# ATMEGA16v4.net
KiCad netlist of a schematic drawn in EAGLE
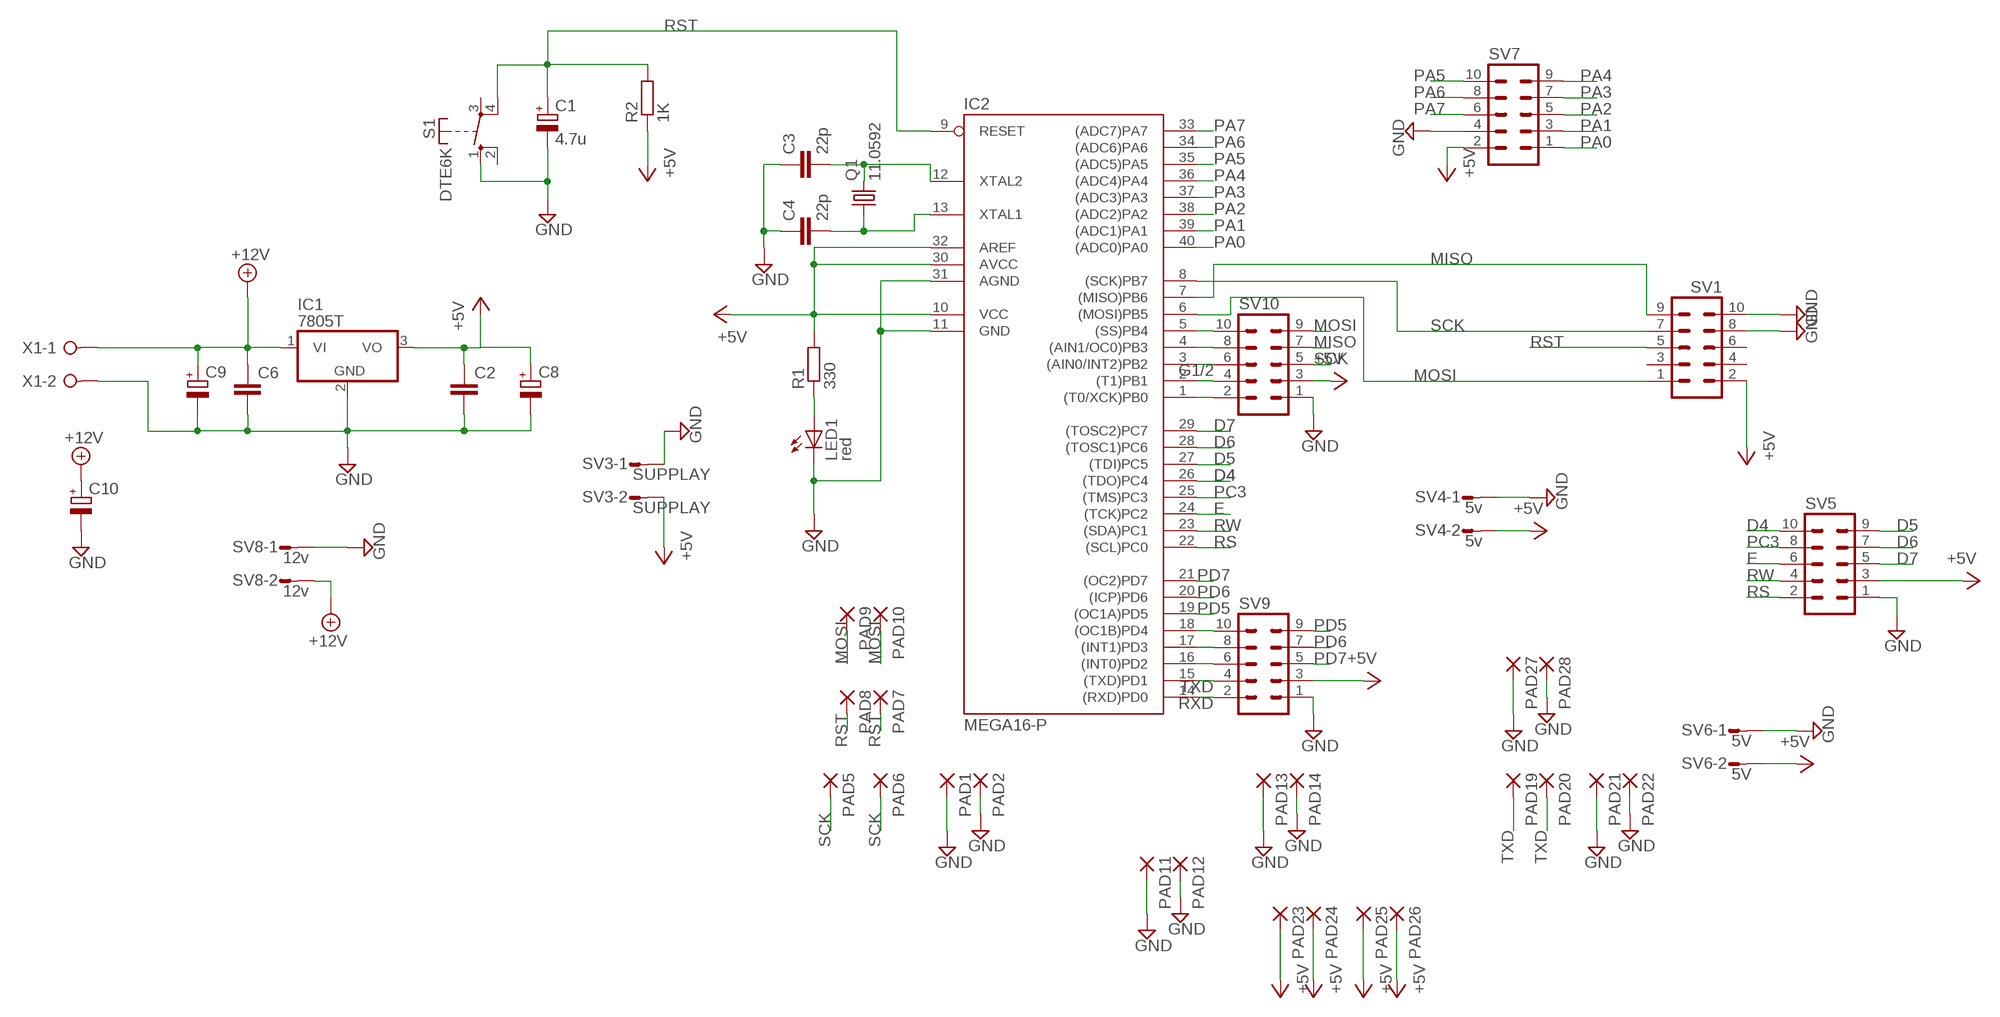
[diagram p0: schematic, sheet 1]
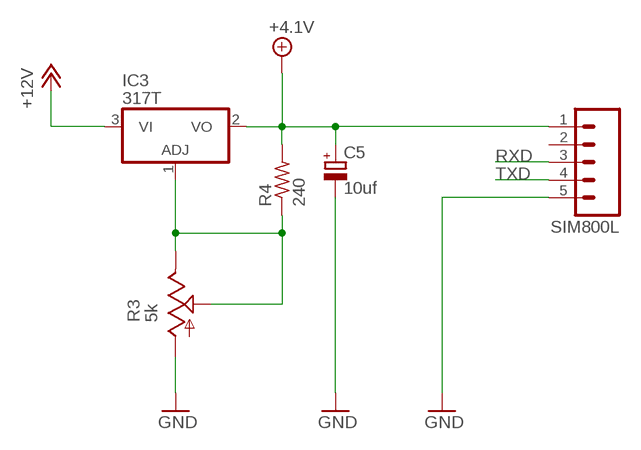
[diagram p1: schematic, sheet 2]

(export (version "E")
  (design (tool "Eeschema 10.0.6"))
  (components
    (comp (ref "C1")
      (value "4.7u")
      (footprint "eagle-import:E2-5")
      (libsource (lib "eagle-import") (part "CPOL-EUE2-5"))
    )
    (comp (ref "C2")
      (value "C-EU050-050X075")
      (footprint "eagle-import:C050-050X075")
      (libsource (lib "eagle-import") (part "C-EU050-050X075"))
    )
    (comp (ref "C3")
      (value "22p")
      (footprint "eagle-import:C025-040X050")
      (libsource (lib "eagle-import") (part "resistor_C-EU025-040X050"))
    )
    (comp (ref "C4")
      (value "22p")
      (footprint "eagle-import:C025-040X050")
      (libsource (lib "eagle-import") (part "resistor_C-EU025-040X050"))
    )
    (comp (ref "C6")
      (value "C-EU050-050X075")
      (footprint "eagle-import:C050-050X075")
      (libsource (lib "eagle-import") (part "C-EU050-050X075"))
    )
    (comp (ref "C8")
      (value "CPOL-EUE2.5-7")
      (footprint "eagle-import:E2,5-7")
      (libsource (lib "eagle-import") (part "CPOL-EUE2.5-7"))
    )
    (comp (ref "C9")
      (value "CPOL-EUE2.5-7")
      (footprint "eagle-import:E2,5-7")
      (libsource (lib "eagle-import") (part "CPOL-EUE2.5-7"))
    )
    (comp (ref "C10")
      (value "CPOL-EUE5-13")
      (footprint "eagle-import:E5-13")
      (libsource (lib "eagle-import") (part "CPOL-EUE5-13"))
    )
    (comp (ref "IC1")
      (value "7805T")
      (footprint "eagle-import:TO220H")
      (libsource (lib "eagle-import") (part "78T05"))
    )
    (comp (ref "IC2")
      (value "MEGA16-P")
      (footprint "eagle-import:DIL40")
      (libsource (lib "eagle-import") (part "MEGA16-P"))
    )
    (comp (ref "LED1")
      (value "red")
      (footprint "eagle-import:LED3MM")
      (libsource (lib "eagle-import") (part "LED3MM"))
    )
    (comp (ref "PAD1")
      (value "1,6/0,9")
      (footprint "eagle-import:1,6_0,9")
      (libsource (lib "eagle-import") (part "1,6/0,9"))
    )
    (comp (ref "PAD2")
      (value "1,6/0,9")
      (footprint "eagle-import:1,6_0,9")
      (libsource (lib "eagle-import") (part "1,6/0,9"))
    )
    (comp (ref "PAD5")
      (value "1,6/0,9")
      (footprint "eagle-import:1,6_0,9")
      (libsource (lib "eagle-import") (part "1,6/0,9"))
    )
    (comp (ref "PAD6")
      (value "1,6/0,9")
      (footprint "eagle-import:1,6_0,9")
      (libsource (lib "eagle-import") (part "1,6/0,9"))
    )
    (comp (ref "PAD7")
      (value "1,6/0,9")
      (footprint "eagle-import:1,6_0,9")
      (libsource (lib "eagle-import") (part "1,6/0,9"))
    )
    (comp (ref "PAD8")
      (value "1,6/0,9")
      (footprint "eagle-import:1,6_0,9")
      (libsource (lib "eagle-import") (part "1,6/0,9"))
    )
    (comp (ref "PAD9")
      (value "1,6/0,9")
      (footprint "eagle-import:1,6_0,9")
      (libsource (lib "eagle-import") (part "1,6/0,9"))
    )
    (comp (ref "PAD10")
      (value "1,6/0,9")
      (footprint "eagle-import:1,6_0,9")
      (libsource (lib "eagle-import") (part "1,6/0,9"))
    )
    (comp (ref "PAD11")
      (value "1,6/0,9")
      (footprint "eagle-import:1,6_0,9")
      (libsource (lib "eagle-import") (part "1,6/0,9"))
    )
    (comp (ref "PAD12")
      (value "1,6/0,9")
      (footprint "eagle-import:1,6_0,9")
      (libsource (lib "eagle-import") (part "1,6/0,9"))
    )
    (comp (ref "PAD13")
      (value "1,6/0,9")
      (footprint "eagle-import:1,6_0,9")
      (libsource (lib "eagle-import") (part "1,6/0,9"))
    )
    (comp (ref "PAD14")
      (value "1,6/0,9")
      (footprint "eagle-import:1,6_0,9")
      (libsource (lib "eagle-import") (part "1,6/0,9"))
    )
    (comp (ref "PAD19")
      (value "1,6/0,9")
      (footprint "eagle-import:1,6_0,9")
      (libsource (lib "eagle-import") (part "1,6/0,9"))
    )
    (comp (ref "PAD20")
      (value "1,6/0,9")
      (footprint "eagle-import:1,6_0,9")
      (libsource (lib "eagle-import") (part "1,6/0,9"))
    )
    (comp (ref "PAD21")
      (value "1,6/0,9")
      (footprint "eagle-import:1,6_0,9")
      (libsource (lib "eagle-import") (part "1,6/0,9"))
    )
    (comp (ref "PAD22")
      (value "1,6/0,9")
      (footprint "eagle-import:1,6_0,9")
      (libsource (lib "eagle-import") (part "1,6/0,9"))
    )
    (comp (ref "PAD23")
      (value "1,6/0,9")
      (footprint "eagle-import:1,6_0,9")
      (libsource (lib "eagle-import") (part "1,6/0,9"))
    )
    (comp (ref "PAD24")
      (value "1,6/0,9")
      (footprint "eagle-import:1,6_0,9")
      (libsource (lib "eagle-import") (part "1,6/0,9"))
    )
    (comp (ref "PAD25")
      (value "1,6/0,9")
      (footprint "eagle-import:1,6_0,9")
      (libsource (lib "eagle-import") (part "1,6/0,9"))
    )
    (comp (ref "PAD26")
      (value "1,6/0,9")
      (footprint "eagle-import:1,6_0,9")
      (libsource (lib "eagle-import") (part "1,6/0,9"))
    )
    (comp (ref "PAD27")
      (value "1,6/0,9")
      (footprint "eagle-import:1,6_0,9")
      (libsource (lib "eagle-import") (part "1,6/0,9"))
    )
    (comp (ref "PAD28")
      (value "1,6/0,9")
      (footprint "eagle-import:1,6_0,9")
      (libsource (lib "eagle-import") (part "1,6/0,9"))
    )
    (comp (ref "Q1")
      (value "11.0592")
      (footprint "eagle-import:HC49U-V")
      (libsource (lib "eagle-import") (part "CRYSTALHC49U-V"))
    )
    (comp (ref "R1")
      (value "330")
      (footprint "eagle-import:0309_12")
      (libsource (lib "eagle-import") (part "R-EU_0309/12"))
    )
    (comp (ref "R2")
      (value "1K")
      (footprint "eagle-import:0309_12")
      (libsource (lib "eagle-import") (part "R-EU_0309/12"))
    )
    (comp (ref "S1")
      (value "DTE6K")
      (footprint "eagle-import:DTE6K")
      (libsource (lib "eagle-import") (part "DTE6K"))
    )
    (comp (ref "SV1")
      (value "ML10")
      (footprint "eagle-import:ML10")
      (libsource (lib "eagle-import") (part "ML10"))
    )
    (comp (ref "SV3")
      (value "SUPPLAY")
      (footprint "eagle-import:L02P")
      (libsource (lib "eagle-import") (part "L02P"))
    )
    (comp (ref "SV4")
      (value "5v")
      (footprint "eagle-import:L02P")
      (libsource (lib "eagle-import") (part "L02P"))
    )
    (comp (ref "SV5")
      (value "ML10")
      (footprint "eagle-import:ML10")
      (libsource (lib "eagle-import") (part "ML10"))
    )
    (comp (ref "SV6")
      (value "5V")
      (footprint "eagle-import:L02P")
      (libsource (lib "eagle-import") (part "L02P"))
    )
    (comp (ref "SV7")
      (value "ML10")
      (footprint "eagle-import:ML10")
      (libsource (lib "eagle-import") (part "ML10"))
    )
    (comp (ref "SV8")
      (value "12v")
      (footprint "eagle-import:L02P")
      (libsource (lib "eagle-import") (part "L02P"))
    )
    (comp (ref "SV9")
      (value "ML10")
      (footprint "eagle-import:ML10")
      (libsource (lib "eagle-import") (part "ML10"))
    )
    (comp (ref "SV10")
      (value "ML10")
      (footprint "eagle-import:ML10")
      (libsource (lib "eagle-import") (part "ML10"))
    )
    (comp (ref "X1")
      (value "W237-02P")
      (footprint "eagle-import:W237-132")
      (libsource (lib "eagle-import") (part "W237-02P"))
    )
    (comp (ref "C5")
      (value "10uf")
      (footprint "eagle-import:E2,5-5")
      (libsource (lib "eagle-import") (part "CPOL-EUE2.5-5"))
    )
    (comp (ref "IC3")
      (value "317T")
      (footprint "eagle-import:TO220H")
      (libsource (lib "eagle-import") (part "317T"))
    )
    (comp (ref "R3")
      (value "5k")
      (footprint "eagle-import:CA6V")
      (libsource (lib "eagle-import") (part "TRIM_US-CA6V"))
    )
    (comp (ref "R4")
      (value "240")
      (footprint "eagle-import:0207_12")
      (libsource (lib "eagle-import") (part "R-US_0207/12"))
    )
    (comp (ref "SIM800L")
      (value "M05")
      (footprint "eagle-import:05P")
      (libsource (lib "eagle-import") (part "M05"))
    )
  )
  (nets
    (net (code "1") (name "+4.1V") (class "Default")
      (node (ref "C5") (pin "+") (pinfunction "+_+") (pintype "passive"))
      (node (ref "IC3") (pin "2") (pinfunction "VO_2") (pintype "passive"))
      (node (ref "R4") (pin "2") (pinfunction "2_2") (pintype "passive"))
      (node (ref "SIM800L") (pin "1") (pinfunction "1_1") (pintype "passive"))
    )
    (net (code "2") (name "+5V") (class "Default")
      (node (ref "C2") (pin "1") (pinfunction "1_1") (pintype "passive"))
      (node (ref "C8") (pin "+") (pinfunction "+_+") (pintype "passive"))
      (node (ref "IC1") (pin "3") (pinfunction "VO_3") (pintype "passive"))
      (node (ref "IC2") (pin "10") (pinfunction "VCC_10") (pintype "power_in"))
      (node (ref "IC2") (pin "30") (pinfunction "AVCC_30") (pintype "power_in"))
      (node (ref "IC2") (pin "32") (pinfunction "AREF_32") (pintype "passive"))
      (node (ref "PAD23") (pin "1") (pinfunction "P_1") (pintype "passive"))
      (node (ref "PAD24") (pin "1") (pinfunction "P_1") (pintype "passive"))
      (node (ref "PAD25") (pin "1") (pinfunction "P_1") (pintype "passive"))
      (node (ref "PAD26") (pin "1") (pinfunction "P_1") (pintype "passive"))
      (node (ref "R1") (pin "2") (pinfunction "2_2") (pintype "passive"))
      (node (ref "R2") (pin "1") (pinfunction "1_1") (pintype "passive"))
      (node (ref "SV1") (pin "2") (pinfunction "2_2") (pintype "passive"))
      (node (ref "SV10") (pin "3") (pinfunction "3_3") (pintype "passive"))
      (node (ref "SV3") (pin "2") (pinfunction "S_2") (pintype "passive"))
      (node (ref "SV4") (pin "2") (pinfunction "S_2") (pintype "passive"))
      (node (ref "SV5") (pin "3") (pinfunction "3_3") (pintype "passive"))
      (node (ref "SV6") (pin "2") (pinfunction "S_2") (pintype "passive"))
      (node (ref "SV7") (pin "2") (pinfunction "2_2") (pintype "passive"))
      (node (ref "SV9") (pin "3") (pinfunction "3_3") (pintype "passive"))
    )
    (net (code "3") (name "+12V") (class "Default")
      (node (ref "C10") (pin "+") (pinfunction "+_+") (pintype "passive"))
      (node (ref "C6") (pin "1") (pinfunction "1_1") (pintype "passive"))
      (node (ref "C9") (pin "+") (pinfunction "+_+") (pintype "passive"))
      (node (ref "IC1") (pin "1") (pinfunction "VI_1") (pintype "input"))
      (node (ref "IC3") (pin "3") (pinfunction "VI_3") (pintype "input"))
      (node (ref "SV8") (pin "2") (pinfunction "S_2") (pintype "passive"))
      (node (ref "X1") (pin "1") (pinfunction "KL_1") (pintype "passive"))
    )
    (net (code "4") (name "D4") (class "Default")
      (node (ref "IC2") (pin "26") (pinfunction "(TDO)PC4_26") (pintype "bidirectional"))
      (node (ref "SV5") (pin "10") (pinfunction "10_10") (pintype "passive"))
    )
    (net (code "5") (name "D5") (class "Default")
      (node (ref "IC2") (pin "27") (pinfunction "(TDI)PC5_27") (pintype "bidirectional"))
      (node (ref "SV5") (pin "9") (pinfunction "9_9") (pintype "passive"))
    )
    (net (code "6") (name "D6") (class "Default")
      (node (ref "IC2") (pin "28") (pinfunction "(TOSC1)PC6_28") (pintype "bidirectional"))
      (node (ref "SV5") (pin "7") (pinfunction "7_7") (pintype "passive"))
    )
    (net (code "7") (name "D7") (class "Default")
      (node (ref "IC2") (pin "29") (pinfunction "(TOSC2)PC7_29") (pintype "bidirectional"))
      (node (ref "SV5") (pin "5") (pinfunction "5_5") (pintype "passive"))
    )
    (net (code "8") (name "E") (class "Default")
      (node (ref "IC2") (pin "24") (pinfunction "(TCK)PC2_24") (pintype "bidirectional"))
      (node (ref "SV5") (pin "6") (pinfunction "6_6") (pintype "passive"))
    )
    (net (code "9") (name "G1{slash}2") (class "Default")
      (node (ref "IC2") (pin "2") (pinfunction "(T1)PB1_2") (pintype "bidirectional"))
      (node (ref "SV10") (pin "4") (pinfunction "4_4") (pintype "passive"))
    )
    (net (code "10") (name "GND") (class "Default")
      (node (ref "C1") (pin "-") (pinfunction "-_-") (pintype "passive"))
      (node (ref "C10") (pin "-") (pinfunction "-_-") (pintype "passive"))
      (node (ref "C2") (pin "2") (pinfunction "2_2") (pintype "passive"))
      (node (ref "C3") (pin "1") (pinfunction "1_1") (pintype "passive"))
      (node (ref "C4") (pin "1") (pinfunction "1_1") (pintype "passive"))
      (node (ref "C5") (pin "-") (pinfunction "-_-") (pintype "passive"))
      (node (ref "C6") (pin "2") (pinfunction "2_2") (pintype "passive"))
      (node (ref "C8") (pin "-") (pinfunction "-_-") (pintype "passive"))
      (node (ref "C9") (pin "-") (pinfunction "-_-") (pintype "passive"))
      (node (ref "IC1") (pin "2") (pinfunction "GND_2") (pintype "passive"))
      (node (ref "IC2") (pin "11") (pinfunction "GND_11") (pintype "power_in"))
      (node (ref "IC2") (pin "31") (pinfunction "AGND_31") (pintype "power_in"))
      (node (ref "LED1") (pin "K") (pinfunction "C_K") (pintype "passive"))
      (node (ref "PAD1") (pin "1") (pinfunction "P_1") (pintype "passive"))
      (node (ref "PAD11") (pin "1") (pinfunction "P_1") (pintype "passive"))
      (node (ref "PAD12") (pin "1") (pinfunction "P_1") (pintype "passive"))
      (node (ref "PAD13") (pin "1") (pinfunction "P_1") (pintype "passive"))
      (node (ref "PAD14") (pin "1") (pinfunction "P_1") (pintype "passive"))
      (node (ref "PAD2") (pin "1") (pinfunction "P_1") (pintype "passive"))
      (node (ref "PAD21") (pin "1") (pinfunction "P_1") (pintype "passive"))
      (node (ref "PAD22") (pin "1") (pinfunction "P_1") (pintype "passive"))
      (node (ref "PAD27") (pin "1") (pinfunction "P_1") (pintype "passive"))
      (node (ref "PAD28") (pin "1") (pinfunction "P_1") (pintype "passive"))
      (node (ref "R3") (pin "A") (pinfunction "A_A") (pintype "passive"))
      (node (ref "S1") (pin "1") (pinfunction "S_1") (pintype "passive"))
      (node (ref "SIM800L") (pin "5") (pinfunction "5_5") (pintype "passive"))
      (node (ref "SV1") (pin "10") (pinfunction "10_10") (pintype "passive"))
      (node (ref "SV1") (pin "8") (pinfunction "8_8") (pintype "passive"))
      (node (ref "SV10") (pin "1") (pinfunction "1_1") (pintype "passive"))
      (node (ref "SV3") (pin "1") (pinfunction "S_1") (pintype "passive"))
      (node (ref "SV4") (pin "1") (pinfunction "S_1") (pintype "passive"))
      (node (ref "SV5") (pin "1") (pinfunction "1_1") (pintype "passive"))
      (node (ref "SV6") (pin "1") (pinfunction "S_1") (pintype "passive"))
      (node (ref "SV7") (pin "4") (pinfunction "4_4") (pintype "passive"))
      (node (ref "SV8") (pin "1") (pinfunction "S_1") (pintype "passive"))
      (node (ref "SV9") (pin "1") (pinfunction "1_1") (pintype "passive"))
      (node (ref "X1") (pin "2") (pinfunction "KL_2") (pintype "passive"))
    )
    (net (code "11") (name "MISO") (class "Default")
      (node (ref "IC2") (pin "7") (pinfunction "(MISO)PB6_7") (pintype "bidirectional"))
      (node (ref "SV1") (pin "9") (pinfunction "9_9") (pintype "passive"))
      (node (ref "SV10") (pin "7") (pinfunction "7_7") (pintype "passive"))
    )
    (net (code "12") (name "MOSI") (class "Default")
      (node (ref "IC2") (pin "6") (pinfunction "(MOSI)PB5_6") (pintype "bidirectional"))
      (node (ref "PAD10") (pin "1") (pinfunction "P_1") (pintype "passive"))
      (node (ref "PAD9") (pin "1") (pinfunction "P_1") (pintype "passive"))
      (node (ref "SV1") (pin "1") (pinfunction "1_1") (pintype "passive"))
      (node (ref "SV10") (pin "9") (pinfunction "9_9") (pintype "passive"))
    )
    (net (code "13") (name "Net-(IC2-(AIN0{slash}INT2)PB2)") (class "Default")
      (node (ref "IC2") (pin "3") (pinfunction "(AIN0/INT2)PB2_3") (pintype "bidirectional"))
      (node (ref "SV10") (pin "6") (pinfunction "6_6") (pintype "passive"))
    )
    (net (code "14") (name "Net-(IC2-(AIN1{slash}OC0)PB3)") (class "Default")
      (node (ref "IC2") (pin "4") (pinfunction "(AIN1/OC0)PB3_4") (pintype "bidirectional"))
      (node (ref "SV10") (pin "8") (pinfunction "8_8") (pintype "passive"))
    )
    (net (code "15") (name "Net-(IC2-(INT0)PD2)") (class "Default")
      (node (ref "IC2") (pin "16") (pinfunction "(INT0)PD2_16") (pintype "bidirectional"))
      (node (ref "SV9") (pin "6") (pinfunction "6_6") (pintype "passive"))
    )
    (net (code "16") (name "Net-(IC2-(INT1)PD3)") (class "Default")
      (node (ref "IC2") (pin "17") (pinfunction "(INT1)PD3_17") (pintype "bidirectional"))
      (node (ref "SV9") (pin "8") (pinfunction "8_8") (pintype "passive"))
    )
    (net (code "17") (name "Net-(IC2-(OC1B)PD4)") (class "Default")
      (node (ref "IC2") (pin "18") (pinfunction "(OC1B)PD4_18") (pintype "bidirectional"))
      (node (ref "SV9") (pin "10") (pinfunction "10_10") (pintype "passive"))
    )
    (net (code "18") (name "Net-(IC2-(SS)PB4)") (class "Default")
      (node (ref "IC2") (pin "5") (pinfunction "(SS)PB4_5") (pintype "bidirectional"))
      (node (ref "SV10") (pin "10") (pinfunction "10_10") (pintype "passive"))
    )
    (net (code "19") (name "Net-(IC2-(T0{slash}XCK)PB0)") (class "Default")
      (node (ref "IC2") (pin "1") (pinfunction "(T0/XCK)PB0_1") (pintype "bidirectional"))
      (node (ref "SV10") (pin "2") (pinfunction "2_2") (pintype "passive"))
    )
    (net (code "20") (name "Net-(IC2-XTAL1)") (class "Default")
      (node (ref "C4") (pin "2") (pinfunction "2_2") (pintype "passive"))
      (node (ref "IC2") (pin "13") (pinfunction "XTAL1_13") (pintype "bidirectional"))
      (node (ref "Q1") (pin "1") (pinfunction "1_1") (pintype "passive"))
    )
    (net (code "21") (name "Net-(IC2-XTAL2)") (class "Default")
      (node (ref "C3") (pin "2") (pinfunction "2_2") (pintype "passive"))
      (node (ref "IC2") (pin "12") (pinfunction "XTAL2_12") (pintype "bidirectional"))
      (node (ref "Q1") (pin "2") (pinfunction "2_2") (pintype "passive"))
    )
    (net (code "22") (name "Net-(IC3-ADJ)") (class "Default")
      (node (ref "IC3") (pin "1") (pinfunction "ADJ_1") (pintype "input"))
      (node (ref "R3") (pin "E") (pinfunction "E_E") (pintype "passive"))
      (node (ref "R3") (pin "S") (pinfunction "S_S") (pintype "passive"))
      (node (ref "R4") (pin "1") (pinfunction "1_1") (pintype "passive"))
    )
    (net (code "23") (name "Net-(LED1-PadA)") (class "Default")
      (node (ref "LED1") (pin "A") (pinfunction "A_A") (pintype "passive"))
      (node (ref "R1") (pin "1") (pinfunction "1_1") (pintype "passive"))
    )
    (net (code "24") (name "PA0") (class "Default")
      (node (ref "IC2") (pin "40") (pinfunction "(ADC0)PA0_40") (pintype "bidirectional"))
      (node (ref "SV7") (pin "1") (pinfunction "1_1") (pintype "passive"))
    )
    (net (code "25") (name "PA1") (class "Default")
      (node (ref "IC2") (pin "39") (pinfunction "(ADC1)PA1_39") (pintype "bidirectional"))
      (node (ref "SV7") (pin "3") (pinfunction "3_3") (pintype "passive"))
    )
    (net (code "26") (name "PA2") (class "Default")
      (node (ref "IC2") (pin "38") (pinfunction "(ADC2)PA2_38") (pintype "bidirectional"))
      (node (ref "SV7") (pin "5") (pinfunction "5_5") (pintype "passive"))
    )
    (net (code "27") (name "PA3") (class "Default")
      (node (ref "IC2") (pin "37") (pinfunction "(ADC3)PA3_37") (pintype "bidirectional"))
      (node (ref "SV7") (pin "7") (pinfunction "7_7") (pintype "passive"))
    )
    (net (code "28") (name "PA4") (class "Default")
      (node (ref "IC2") (pin "36") (pinfunction "(ADC4)PA4_36") (pintype "bidirectional"))
      (node (ref "SV7") (pin "9") (pinfunction "9_9") (pintype "passive"))
    )
    (net (code "29") (name "PA5") (class "Default")
      (node (ref "IC2") (pin "35") (pinfunction "(ADC5)PA5_35") (pintype "bidirectional"))
      (node (ref "SV7") (pin "10") (pinfunction "10_10") (pintype "passive"))
    )
    (net (code "30") (name "PA6") (class "Default")
      (node (ref "IC2") (pin "34") (pinfunction "(ADC6)PA6_34") (pintype "bidirectional"))
      (node (ref "SV7") (pin "8") (pinfunction "8_8") (pintype "passive"))
    )
    (net (code "31") (name "PA7") (class "Default")
      (node (ref "IC2") (pin "33") (pinfunction "(ADC7)PA7_33") (pintype "bidirectional"))
      (node (ref "SV7") (pin "6") (pinfunction "6_6") (pintype "passive"))
    )
    (net (code "32") (name "PC3") (class "Default")
      (node (ref "IC2") (pin "25") (pinfunction "(TMS)PC3_25") (pintype "bidirectional"))
      (node (ref "SV5") (pin "8") (pinfunction "8_8") (pintype "passive"))
    )
    (net (code "33") (name "PD5") (class "Default")
      (node (ref "IC2") (pin "19") (pinfunction "(OC1A)PD5_19") (pintype "bidirectional"))
      (node (ref "SV9") (pin "9") (pinfunction "9_9") (pintype "passive"))
    )
    (net (code "34") (name "PD6") (class "Default")
      (node (ref "IC2") (pin "20") (pinfunction "(ICP)PD6_20") (pintype "bidirectional"))
      (node (ref "SV9") (pin "7") (pinfunction "7_7") (pintype "passive"))
    )
    (net (code "35") (name "PD7") (class "Default")
      (node (ref "IC2") (pin "21") (pinfunction "(OC2)PD7_21") (pintype "bidirectional"))
      (node (ref "SV9") (pin "5") (pinfunction "5_5") (pintype "passive"))
    )
    (net (code "36") (name "RS") (class "Default")
      (node (ref "IC2") (pin "22") (pinfunction "(SCL)PC0_22") (pintype "bidirectional"))
      (node (ref "SV5") (pin "2") (pinfunction "2_2") (pintype "passive"))
    )
    (net (code "37") (name "RST") (class "Default")
      (node (ref "C1") (pin "+") (pinfunction "+_+") (pintype "passive"))
      (node (ref "IC2") (pin "9") (pinfunction "RESET_9") (pintype "input"))
      (node (ref "PAD7") (pin "1") (pinfunction "P_1") (pintype "passive"))
      (node (ref "PAD8") (pin "1") (pinfunction "P_1") (pintype "passive"))
      (node (ref "R2") (pin "2") (pinfunction "2_2") (pintype "passive"))
      (node (ref "S1") (pin "4") (pinfunction "P_4") (pintype "passive"))
      (node (ref "SV1") (pin "5") (pinfunction "5_5") (pintype "passive"))
    )
    (net (code "38") (name "RW") (class "Default")
      (node (ref "IC2") (pin "23") (pinfunction "(SDA)PC1_23") (pintype "bidirectional"))
      (node (ref "SV5") (pin "4") (pinfunction "4_4") (pintype "passive"))
    )
    (net (code "39") (name "RXD") (class "Default")
      (node (ref "IC2") (pin "14") (pinfunction "(RXD)PD0_14") (pintype "bidirectional"))
      (node (ref "SIM800L") (pin "3") (pinfunction "3_3") (pintype "passive"))
      (node (ref "SV9") (pin "2") (pinfunction "2_2") (pintype "passive"))
    )
    (net (code "40") (name "SCK") (class "Default")
      (node (ref "IC2") (pin "8") (pinfunction "(SCK)PB7_8") (pintype "bidirectional"))
      (node (ref "PAD5") (pin "1") (pinfunction "P_1") (pintype "passive"))
      (node (ref "PAD6") (pin "1") (pinfunction "P_1") (pintype "passive"))
      (node (ref "SV1") (pin "7") (pinfunction "7_7") (pintype "passive"))
      (node (ref "SV10") (pin "5") (pinfunction "5_5") (pintype "passive"))
    )
    (net (code "41") (name "TXD") (class "Default")
      (node (ref "IC2") (pin "15") (pinfunction "(TXD)PD1_15") (pintype "bidirectional"))
      (node (ref "PAD19") (pin "1") (pinfunction "P_1") (pintype "passive"))
      (node (ref "PAD20") (pin "1") (pinfunction "P_1") (pintype "passive"))
      (node (ref "SIM800L") (pin "4") (pinfunction "4_4") (pintype "passive"))
      (node (ref "SV9") (pin "4") (pinfunction "4_4") (pintype "passive"))
    )
    (net (code "42") (name "unconnected-(S1-P-Pad3)") (class "Default")
      (node (ref "S1") (pin "3") (pinfunction "P_3") (pintype "passive"))
    )
    (net (code "43") (name "unconnected-(S1-S-Pad2)") (class "Default")
      (node (ref "S1") (pin "2") (pinfunction "S_2") (pintype "passive"))
    )
    (net (code "44") (name "unconnected-(SIM800L-Pad2)") (class "Default")
      (node (ref "SIM800L") (pin "2") (pinfunction "2_2") (pintype "passive"))
    )
    (net (code "45") (name "unconnected-(SV1-Pad3)") (class "Default")
      (node (ref "SV1") (pin "3") (pinfunction "3_3") (pintype "passive"))
    )
    (net (code "46") (name "unconnected-(SV1-Pad4)") (class "Default")
      (node (ref "SV1") (pin "4") (pinfunction "4_4") (pintype "passive"))
    )
    (net (code "47") (name "unconnected-(SV1-Pad6)") (class "Default")
      (node (ref "SV1") (pin "6") (pinfunction "6_6") (pintype "passive"))
    )
  )
)
